# butterworth5-8th.net
KiCad netlist of a schematic drawn in Altium Designer
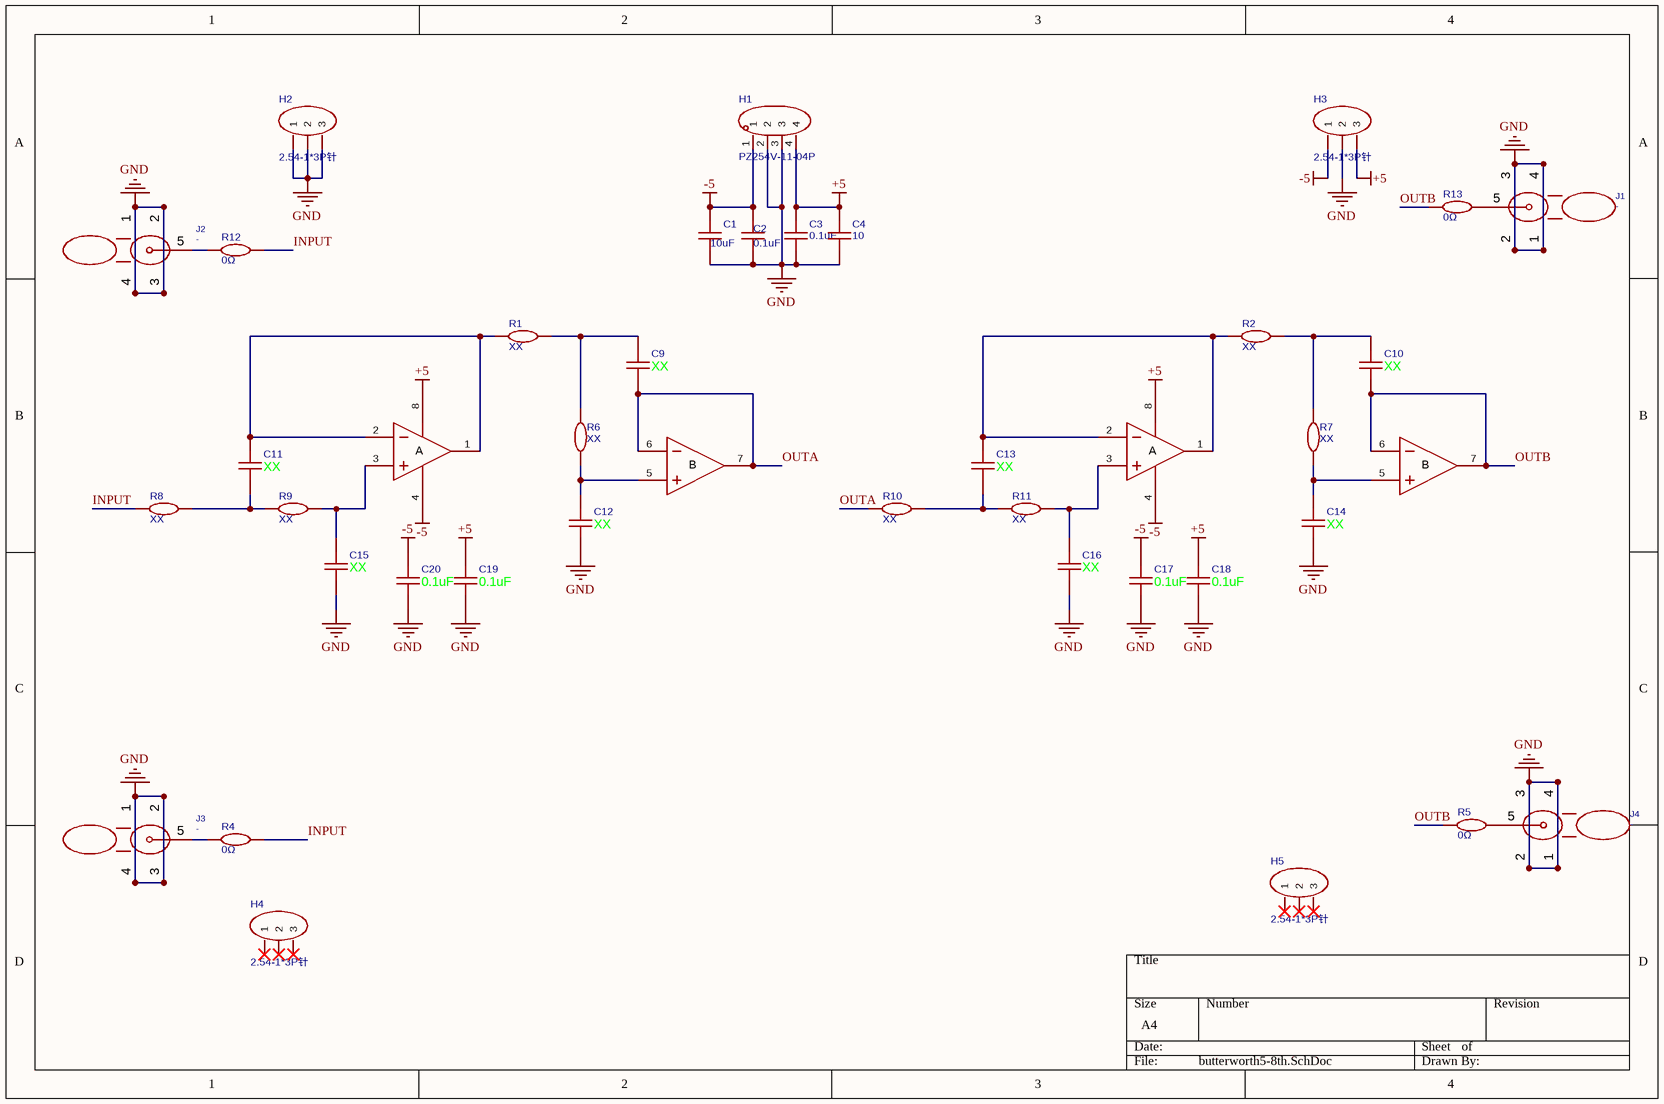
[diagram p0: butterworth5-8th.SchDoc]

(export (version "E")
  (design (tool "Eeschema 10.0.6"))
  (components
    (comp (ref "C1")
      (value "10uF")
      (footprint "C0603")
      (description "CAP_0603")
      (libsource (lib "Passives") (part "CAP_0603"))
    )
    (comp (ref "C2")
      (value "0.1uF")
      (footprint "C0603")
      (description "CAP_0603")
      (libsource (lib "Passives") (part "CAP_0603"))
    )
    (comp (ref "C3")
      (value "0.1uF")
      (footprint "C0603")
      (description "CAP_0603")
      (libsource (lib "Passives") (part "CAP_0603"))
    )
    (comp (ref "C4")
      (value "10")
      (footprint "C0603")
      (description "CAP_0603")
      (libsource (lib "Passives") (part "CAP_0603"))
    )
    (comp (ref "C9")
      (value "XX")
      (footprint "C0805")
      (description "容值:100nF;精度:±10%;额定电压:50V;温度系数:X7R;")
      (fields (field (name "MANUFACTURER") "YAGEO(国巨)") (field (name "MANUFACTURERPART") "CC0805KRX7R9BB104"))
      (libsource (lib "Passives") (part "cc0805krx7r9bb104"))
    )
    (comp (ref "C10")
      (value "XX")
      (footprint "C0805")
      (description "容值:100nF;精度:±10%;额定电压:50V;温度系数:X7R;")
      (fields (field (name "MANUFACTURER") "YAGEO(国巨)") (field (name "MANUFACTURERPART") "CC0805KRX7R9BB104"))
      (libsource (lib "Passives") (part "cc0805krx7r9bb104"))
    )
    (comp (ref "C11")
      (value "XX")
      (footprint "C0805")
      (description "容值:100nF;精度:±10%;额定电压:50V;温度系数:X7R;")
      (fields (field (name "MANUFACTURER") "YAGEO(国巨)") (field (name "MANUFACTURERPART") "CC0805KRX7R9BB104"))
      (libsource (lib "Passives") (part "cc0805krx7r9bb104"))
    )
    (comp (ref "C12")
      (value "XX")
      (footprint "C0805")
      (description "容值:100nF;精度:±10%;额定电压:50V;温度系数:X7R;")
      (fields (field (name "MANUFACTURER") "YAGEO(国巨)") (field (name "MANUFACTURERPART") "CC0805KRX7R9BB104"))
      (libsource (lib "Passives") (part "cc0805krx7r9bb104"))
    )
    (comp (ref "C13")
      (value "XX")
      (footprint "C0805")
      (description "容值:100nF;精度:±10%;额定电压:50V;温度系数:X7R;")
      (fields (field (name "MANUFACTURER") "YAGEO(国巨)") (field (name "MANUFACTURERPART") "CC0805KRX7R9BB104"))
      (libsource (lib "Passives") (part "cc0805krx7r9bb104"))
    )
    (comp (ref "C14")
      (value "XX")
      (footprint "C0805")
      (description "容值:100nF;精度:±10%;额定电压:50V;温度系数:X7R;")
      (fields (field (name "MANUFACTURER") "YAGEO(国巨)") (field (name "MANUFACTURERPART") "CC0805KRX7R9BB104"))
      (libsource (lib "Passives") (part "cc0805krx7r9bb104"))
    )
    (comp (ref "C15")
      (value "XX")
      (footprint "C0805")
      (description "容值:100nF;精度:±10%;额定电压:50V;温度系数:X7R;")
      (fields (field (name "MANUFACTURER") "YAGEO(国巨)") (field (name "MANUFACTURERPART") "CC0805KRX7R9BB104"))
      (libsource (lib "Passives") (part "cc0805krx7r9bb104"))
    )
    (comp (ref "C16")
      (value "XX")
      (footprint "C0805")
      (description "容值:100nF;精度:±10%;额定电压:50V;温度系数:X7R;")
      (fields (field (name "MANUFACTURER") "YAGEO(国巨)") (field (name "MANUFACTURERPART") "CC0805KRX7R9BB104"))
      (libsource (lib "Passives") (part "cc0805krx7r9bb104"))
    )
    (comp (ref "C17")
      (value "0.1uF")
      (footprint "C0805")
      (description "容值:100nF;精度:±10%;额定电压:50V;温度系数:X7R;")
      (fields (field (name "MANUFACTURER") "YAGEO(国巨)") (field (name "MANUFACTURERPART") "CC0805KRX7R9BB104"))
      (libsource (lib "Passives") (part "cc0805krx7r9bb104"))
    )
    (comp (ref "C18")
      (value "0.1uF")
      (footprint "C0805")
      (description "容值:100nF;精度:±10%;额定电压:50V;温度系数:X7R;")
      (fields (field (name "MANUFACTURER") "YAGEO(国巨)") (field (name "MANUFACTURERPART") "CC0805KRX7R9BB104"))
      (libsource (lib "Passives") (part "cc0805krx7r9bb104"))
    )
    (comp (ref "C19")
      (value "0.1uF")
      (footprint "C0805")
      (description "容值:100nF;精度:±10%;额定电压:50V;温度系数:X7R;")
      (fields (field (name "MANUFACTURER") "YAGEO(国巨)") (field (name "MANUFACTURERPART") "CC0805KRX7R9BB104"))
      (libsource (lib "Passives") (part "cc0805krx7r9bb104"))
    )
    (comp (ref "C20")
      (value "0.1uF")
      (footprint "C0805")
      (description "容值:100nF;精度:±10%;额定电压:50V;温度系数:X7R;")
      (fields (field (name "MANUFACTURER") "YAGEO(国巨)") (field (name "MANUFACTURERPART") "CC0805KRX7R9BB104"))
      (libsource (lib "Passives") (part "cc0805krx7r9bb104"))
    )
    (comp (ref "H1")
      (value "PZ254V-11-04P")
      (footprint "HDR-TH_4P-P2.54-V-M")
      (fields (field (name "MANUFACTURER") "XFCN(兴飞)"))
      (libsource (lib "Connectors") (part "PZ254V-11-04P"))
    )
    (comp (ref "H2")
      (value "2.54-1*3P针")
      (footprint "HDR-TH_3P-P2.54-V-M-1")
      (fields (field (name "MANUFACTURER") "BOOMELE(博穆精密)"))
      (libsource (lib "Connectors") (part "2.54-1*3P针"))
    )
    (comp (ref "H3")
      (value "2.54-1*3P针")
      (footprint "HDR-TH_3P-P2.54-V-M-1")
      (fields (field (name "MANUFACTURER") "BOOMELE(博穆精密)"))
      (libsource (lib "Connectors") (part "2.54-1*3P针"))
    )
    (comp (ref "H4")
      (value "2.54-1*3P针")
      (footprint "HDR-TH_3P-P2.54-V-M-1")
      (fields (field (name "MANUFACTURER") "BOOMELE(博穆精密)"))
      (libsource (lib "Connectors") (part "2.54-1*3P针"))
    )
    (comp (ref "H5")
      (value "2.54-1*3P针")
      (footprint "HDR-TH_3P-P2.54-V-M-1")
      (fields (field (name "MANUFACTURER") "BOOMELE(博穆精密)"))
      (libsource (lib "Connectors") (part "2.54-1*3P针"))
    )
    (comp (ref "J1")
      (value "-")
      (footprint "SMA-TH_BWSMA-KWE-Z001")
      (description "连接器类型:板端;接口类型:内孔;端口数量:1;接口直径:6.2mm;接口长度/高度:-;频率:-;射频系列:SMA;阻抗:50Ω;样式:弯头;工作温度:-;")
      (fields
        (field (name "MANUFACTURER") "BAT WIRELESS(蝙蝠无线)")
        (field (name "MANUFACTURER PART") "BWSMA-KWE-Z001")
      )
      (libsource (lib "Connectors") (part "BWSMA-KWE-Z001"))
    )
    (comp (ref "J2")
      (value "-")
      (footprint "SMA-TH_BWSMA-KWE-Z001")
      (description "连接器类型:板端;接口类型:内孔;端口数量:1;接口直径:6.2mm;接口长度/高度:-;频率:-;射频系列:SMA;阻抗:50Ω;样式:弯头;工作温度:-;")
      (fields
        (field (name "MANUFACTURER") "BAT WIRELESS(蝙蝠无线)")
        (field (name "MANUFACTURER PART") "BWSMA-KWE-Z001")
      )
      (libsource (lib "Connectors") (part "BWSMA-KWE-Z001"))
    )
    (comp (ref "J3")
      (value "-")
      (footprint "SMA-TH_BWSMA-KWE-Z001")
      (description "连接器类型:板端;接口类型:内孔;端口数量:1;接口直径:6.2mm;接口长度/高度:-;频率:-;射频系列:SMA;阻抗:50Ω;样式:弯头;工作温度:-;")
      (fields
        (field (name "MANUFACTURER") "BAT WIRELESS(蝙蝠无线)")
        (field (name "MANUFACTURER PART") "BWSMA-KWE-Z001")
      )
      (libsource (lib "Connectors") (part "BWSMA-KWE-Z001"))
    )
    (comp (ref "J4")
      (value "-")
      (footprint "SMA-TH_BWSMA-KWE-Z001")
      (description "连接器类型:板端;接口类型:内孔;端口数量:1;接口直径:6.2mm;接口长度/高度:-;频率:-;射频系列:SMA;阻抗:50Ω;样式:弯头;工作温度:-;")
      (fields
        (field (name "MANUFACTURER") "BAT WIRELESS(蝙蝠无线)")
        (field (name "MANUFACTURER PART") "BWSMA-KWE-Z001")
      )
      (libsource (lib "Connectors") (part "BWSMA-KWE-Z001"))
    )
    (comp (ref "R1")
      (value "XX")
      (footprint "R0805")
      (description "Res_0805")
      (libsource (lib "Passives") (part "Res_0805"))
    )
    (comp (ref "R2")
      (value "XX")
      (footprint "R0805")
      (description "Res_0805")
      (libsource (lib "Passives") (part "Res_0805"))
    )
    (comp (ref "R4")
      (value "0Ω")
      (footprint "R0805")
      (description "Res_0805")
      (libsource (lib "Passives") (part "Res_0805"))
    )
    (comp (ref "R5")
      (value "0Ω")
      (footprint "R0805")
      (description "Res_0805")
      (libsource (lib "Passives") (part "Res_0805"))
    )
    (comp (ref "R6")
      (value "XX")
      (footprint "R0805")
      (description "Res_0805")
      (libsource (lib "Passives") (part "Res_0805"))
    )
    (comp (ref "R7")
      (value "XX")
      (footprint "R0805")
      (description "Res_0805")
      (libsource (lib "Passives") (part "Res_0805"))
    )
    (comp (ref "R8")
      (value "XX")
      (footprint "R0805")
      (description "Res_0805")
      (libsource (lib "Passives") (part "Res_0805"))
    )
    (comp (ref "R9")
      (value "XX")
      (footprint "R0805")
      (description "Res_0805")
      (libsource (lib "Passives") (part "Res_0805"))
    )
    (comp (ref "R10")
      (value "XX")
      (footprint "R0805")
      (description "Res_0805")
      (libsource (lib "Passives") (part "Res_0805"))
    )
    (comp (ref "R11")
      (value "XX")
      (footprint "R0805")
      (description "Res_0805")
      (libsource (lib "Passives") (part "Res_0805"))
    )
    (comp (ref "R12")
      (value "0Ω")
      (footprint "R0805")
      (description "Res_0805")
      (libsource (lib "Passives") (part "Res_0805"))
    )
    (comp (ref "R13")
      (value "0Ω")
      (footprint "R0805")
      (description "Res_0805")
      (libsource (lib "Passives") (part "Res_0805"))
    )
    (comp (ref "U1")
      (value "opa2140aid")
      (footprint "SOIC-8_L4.9-W3.9-P1.27-LS6.0-BL")
      (description "放大器数:2;轨到轨:轨到轨输入,轨到轨输出;增益带宽积(GBW):11MHz;输入失调电压(Vos):120uV;压摆率(SR):20V/us;输入偏置电流(Ib):10pA;")
      (fields (field (name "MANUFACTURER") "TI(德州仪器)") (field (name "MANUFACTURERPART") "OPA2140AID"))
      (libsource (lib "ICs") (part "opa2140aid"))
    )
    (comp (ref "U2")
      (value "opa2140aid")
      (footprint "SOIC-8_L4.9-W3.9-P1.27-LS6.0-BL")
      (description "放大器数:2;轨到轨:轨到轨输入,轨到轨输出;增益带宽积(GBW):11MHz;输入失调电压(Vos):120uV;压摆率(SR):20V/us;输入偏置电流(Ib):10pA;")
      (fields (field (name "MANUFACTURER") "TI(德州仪器)") (field (name "MANUFACTURERPART") "OPA2140AID"))
      (libsource (lib "ICs") (part "opa2140aid"))
    )
  )
  (nets
    (net (code "1") (name "+5") (class "Default")
      (node (ref "C18") (pin "2") (pinfunction "2_2") (pintype "passive"))
      (node (ref "C19") (pin "2") (pinfunction "2_2") (pintype "passive"))
      (node (ref "C3") (pin "2") (pinfunction "2_2") (pintype "passive"))
      (node (ref "C4") (pin "2") (pinfunction "2_2") (pintype "passive"))
      (node (ref "H1") (pin "4") (pinfunction "4_4") (pintype "passive"))
      (node (ref "H3") (pin "3") (pinfunction "3_3") (pintype "passive"))
      (node (ref "U1") (pin "8") (pinfunction "V+_8") (pintype "passive"))
      (node (ref "U2") (pin "8") (pinfunction "V+_8") (pintype "passive"))
    )
    (net (code "2") (name "-5") (class "Default")
      (node (ref "C1") (pin "2") (pinfunction "2_2") (pintype "passive"))
      (node (ref "C17") (pin "2") (pinfunction "2_2") (pintype "passive"))
      (node (ref "C2") (pin "2") (pinfunction "2_2") (pintype "passive"))
      (node (ref "C20") (pin "2") (pinfunction "2_2") (pintype "passive"))
      (node (ref "H1") (pin "1") (pinfunction "1_1") (pintype "passive"))
      (node (ref "H3") (pin "1") (pinfunction "1_1") (pintype "passive"))
      (node (ref "U1") (pin "4") (pinfunction "V-_4") (pintype "passive"))
      (node (ref "U2") (pin "4") (pinfunction "V-_4") (pintype "passive"))
    )
    (net (code "3") (name "/INPUT") (class "Default")
      (node (ref "R12") (pin "2") (pinfunction "2_2") (pintype "passive"))
      (node (ref "R4") (pin "2") (pinfunction "2_2") (pintype "passive"))
      (node (ref "R8") (pin "1") (pinfunction "1_1") (pintype "passive"))
    )
    (net (code "4") (name "/OUTA") (class "Default")
      (node (ref "C9") (pin "1") (pinfunction "1_1") (pintype "passive"))
      (node (ref "R10") (pin "1") (pinfunction "1_1") (pintype "passive"))
      (node (ref "U2") (pin "6") (pinfunction "INB-_6") (pintype "passive"))
      (node (ref "U2") (pin "7") (pinfunction "OUTB_7") (pintype "passive"))
    )
    (net (code "5") (name "/OUTB") (class "Default")
      (node (ref "C10") (pin "1") (pinfunction "1_1") (pintype "passive"))
      (node (ref "R13") (pin "1") (pinfunction "1_1") (pintype "passive"))
      (node (ref "R5") (pin "1") (pinfunction "1_1") (pintype "passive"))
      (node (ref "U1") (pin "6") (pinfunction "INB-_6") (pintype "passive"))
      (node (ref "U1") (pin "7") (pinfunction "OUTB_7") (pintype "passive"))
    )
    (net (code "6") (name "GND") (class "Default")
      (node (ref "C1") (pin "1") (pinfunction "1_1") (pintype "passive"))
      (node (ref "C12") (pin "1") (pinfunction "1_1") (pintype "passive"))
      (node (ref "C14") (pin "1") (pinfunction "1_1") (pintype "passive"))
      (node (ref "C15") (pin "1") (pinfunction "1_1") (pintype "passive"))
      (node (ref "C16") (pin "1") (pinfunction "1_1") (pintype "passive"))
      (node (ref "C17") (pin "1") (pinfunction "1_1") (pintype "passive"))
      (node (ref "C18") (pin "1") (pinfunction "1_1") (pintype "passive"))
      (node (ref "C19") (pin "1") (pinfunction "1_1") (pintype "passive"))
      (node (ref "C2") (pin "1") (pinfunction "1_1") (pintype "passive"))
      (node (ref "C20") (pin "1") (pinfunction "1_1") (pintype "passive"))
      (node (ref "C3") (pin "1") (pinfunction "1_1") (pintype "passive"))
      (node (ref "C4") (pin "1") (pinfunction "1_1") (pintype "passive"))
      (node (ref "H1") (pin "2") (pinfunction "2_2") (pintype "passive"))
      (node (ref "H1") (pin "3") (pinfunction "3_3") (pintype "passive"))
      (node (ref "H2") (pin "1") (pinfunction "1_1") (pintype "passive"))
      (node (ref "H2") (pin "2") (pinfunction "2_2") (pintype "passive"))
      (node (ref "H2") (pin "3") (pinfunction "3_3") (pintype "passive"))
      (node (ref "H3") (pin "2") (pinfunction "2_2") (pintype "passive"))
      (node (ref "J1") (pin "1") (pinfunction "1_1") (pintype "passive"))
      (node (ref "J1") (pin "2") (pinfunction "2_2") (pintype "passive"))
      (node (ref "J1") (pin "3") (pinfunction "3_3") (pintype "passive"))
      (node (ref "J1") (pin "4") (pinfunction "4_4") (pintype "passive"))
      (node (ref "J2") (pin "1") (pinfunction "1_1") (pintype "passive"))
      (node (ref "J2") (pin "2") (pinfunction "2_2") (pintype "passive"))
      (node (ref "J2") (pin "3") (pinfunction "3_3") (pintype "passive"))
      (node (ref "J2") (pin "4") (pinfunction "4_4") (pintype "passive"))
      (node (ref "J3") (pin "1") (pinfunction "1_1") (pintype "passive"))
      (node (ref "J3") (pin "2") (pinfunction "2_2") (pintype "passive"))
      (node (ref "J3") (pin "3") (pinfunction "3_3") (pintype "passive"))
      (node (ref "J3") (pin "4") (pinfunction "4_4") (pintype "passive"))
      (node (ref "J4") (pin "1") (pinfunction "1_1") (pintype "passive"))
      (node (ref "J4") (pin "2") (pinfunction "2_2") (pintype "passive"))
      (node (ref "J4") (pin "3") (pinfunction "3_3") (pintype "passive"))
      (node (ref "J4") (pin "4") (pinfunction "4_4") (pintype "passive"))
    )
    (net (code "7") (name "Net-(C9-Pad2)") (class "Default")
      (node (ref "C9") (pin "2") (pinfunction "2_2") (pintype "passive"))
      (node (ref "R1") (pin "2") (pinfunction "2_2") (pintype "passive"))
      (node (ref "R6") (pin "1") (pinfunction "1_1") (pintype "passive"))
    )
    (net (code "8") (name "Net-(C10-Pad2)") (class "Default")
      (node (ref "C10") (pin "2") (pinfunction "2_2") (pintype "passive"))
      (node (ref "R2") (pin "2") (pinfunction "2_2") (pintype "passive"))
      (node (ref "R7") (pin "1") (pinfunction "1_1") (pintype "passive"))
    )
    (net (code "9") (name "Net-(C11-Pad1)") (class "Default")
      (node (ref "C11") (pin "1") (pinfunction "1_1") (pintype "passive"))
      (node (ref "R8") (pin "2") (pinfunction "2_2") (pintype "passive"))
      (node (ref "R9") (pin "1") (pinfunction "1_1") (pintype "passive"))
    )
    (net (code "10") (name "Net-(C13-Pad1)") (class "Default")
      (node (ref "C13") (pin "1") (pinfunction "1_1") (pintype "passive"))
      (node (ref "R10") (pin "2") (pinfunction "2_2") (pintype "passive"))
      (node (ref "R11") (pin "1") (pinfunction "1_1") (pintype "passive"))
    )
    (net (code "11") (name "Net-(J1-Pad5)") (class "Default")
      (node (ref "J1") (pin "5") (pinfunction "5_5") (pintype "passive"))
      (node (ref "R13") (pin "2") (pinfunction "2_2") (pintype "passive"))
    )
    (net (code "12") (name "Net-(J2-Pad5)") (class "Default")
      (node (ref "J2") (pin "5") (pinfunction "5_5") (pintype "passive"))
      (node (ref "R12") (pin "1") (pinfunction "1_1") (pintype "passive"))
    )
    (net (code "13") (name "Net-(J3-Pad5)") (class "Default")
      (node (ref "J3") (pin "5") (pinfunction "5_5") (pintype "passive"))
      (node (ref "R4") (pin "1") (pinfunction "1_1") (pintype "passive"))
    )
    (net (code "14") (name "Net-(J4-Pad5)") (class "Default")
      (node (ref "J4") (pin "5") (pinfunction "5_5") (pintype "passive"))
      (node (ref "R5") (pin "2") (pinfunction "2_2") (pintype "passive"))
    )
    (net (code "15") (name "Net-(U1A-INA+)") (class "Default")
      (node (ref "C16") (pin "2") (pinfunction "2_2") (pintype "passive"))
      (node (ref "R11") (pin "2") (pinfunction "2_2") (pintype "passive"))
      (node (ref "U1") (pin "3") (pinfunction "INA+_3") (pintype "passive"))
    )
    (net (code "16") (name "Net-(U1A-INA-)") (class "Default")
      (node (ref "C13") (pin "2") (pinfunction "2_2") (pintype "passive"))
      (node (ref "R2") (pin "1") (pinfunction "1_1") (pintype "passive"))
      (node (ref "U1") (pin "1") (pinfunction "OUTA_1") (pintype "passive"))
      (node (ref "U1") (pin "2") (pinfunction "INA-_2") (pintype "passive"))
    )
    (net (code "17") (name "Net-(U1B-INB+)") (class "Default")
      (node (ref "C14") (pin "2") (pinfunction "2_2") (pintype "passive"))
      (node (ref "R7") (pin "2") (pinfunction "2_2") (pintype "passive"))
      (node (ref "U1") (pin "5") (pinfunction "INB+_5") (pintype "passive"))
    )
    (net (code "18") (name "Net-(U2A-INA+)") (class "Default")
      (node (ref "C15") (pin "2") (pinfunction "2_2") (pintype "passive"))
      (node (ref "R9") (pin "2") (pinfunction "2_2") (pintype "passive"))
      (node (ref "U2") (pin "3") (pinfunction "INA+_3") (pintype "passive"))
    )
    (net (code "19") (name "Net-(U2A-INA-)") (class "Default")
      (node (ref "C11") (pin "2") (pinfunction "2_2") (pintype "passive"))
      (node (ref "R1") (pin "1") (pinfunction "1_1") (pintype "passive"))
      (node (ref "U2") (pin "1") (pinfunction "OUTA_1") (pintype "passive"))
      (node (ref "U2") (pin "2") (pinfunction "INA-_2") (pintype "passive"))
    )
    (net (code "20") (name "Net-(U2B-INB+)") (class "Default")
      (node (ref "C12") (pin "2") (pinfunction "2_2") (pintype "passive"))
      (node (ref "R6") (pin "2") (pinfunction "2_2") (pintype "passive"))
      (node (ref "U2") (pin "5") (pinfunction "INB+_5") (pintype "passive"))
    )
    (net (code "21") (name "unconnected-(H4-Pad1)") (class "Default")
      (node (ref "H4") (pin "1") (pinfunction "1_1") (pintype "passive+no_connect"))
    )
    (net (code "22") (name "unconnected-(H4-Pad2)") (class "Default")
      (node (ref "H4") (pin "2") (pinfunction "2_2") (pintype "passive+no_connect"))
    )
    (net (code "23") (name "unconnected-(H4-Pad3)") (class "Default")
      (node (ref "H4") (pin "3") (pinfunction "3_3") (pintype "passive+no_connect"))
    )
    (net (code "24") (name "unconnected-(H5-Pad1)") (class "Default")
      (node (ref "H5") (pin "1") (pinfunction "1_1") (pintype "passive+no_connect"))
    )
    (net (code "25") (name "unconnected-(H5-Pad2)") (class "Default")
      (node (ref "H5") (pin "2") (pinfunction "2_2") (pintype "passive+no_connect"))
    )
    (net (code "26") (name "unconnected-(H5-Pad3)") (class "Default")
      (node (ref "H5") (pin "3") (pinfunction "3_3") (pintype "passive+no_connect"))
    )
  )
)
